# Power_Supply_Currentsensors.net
KiCad netlist of a schematic drawn in Altium Designer
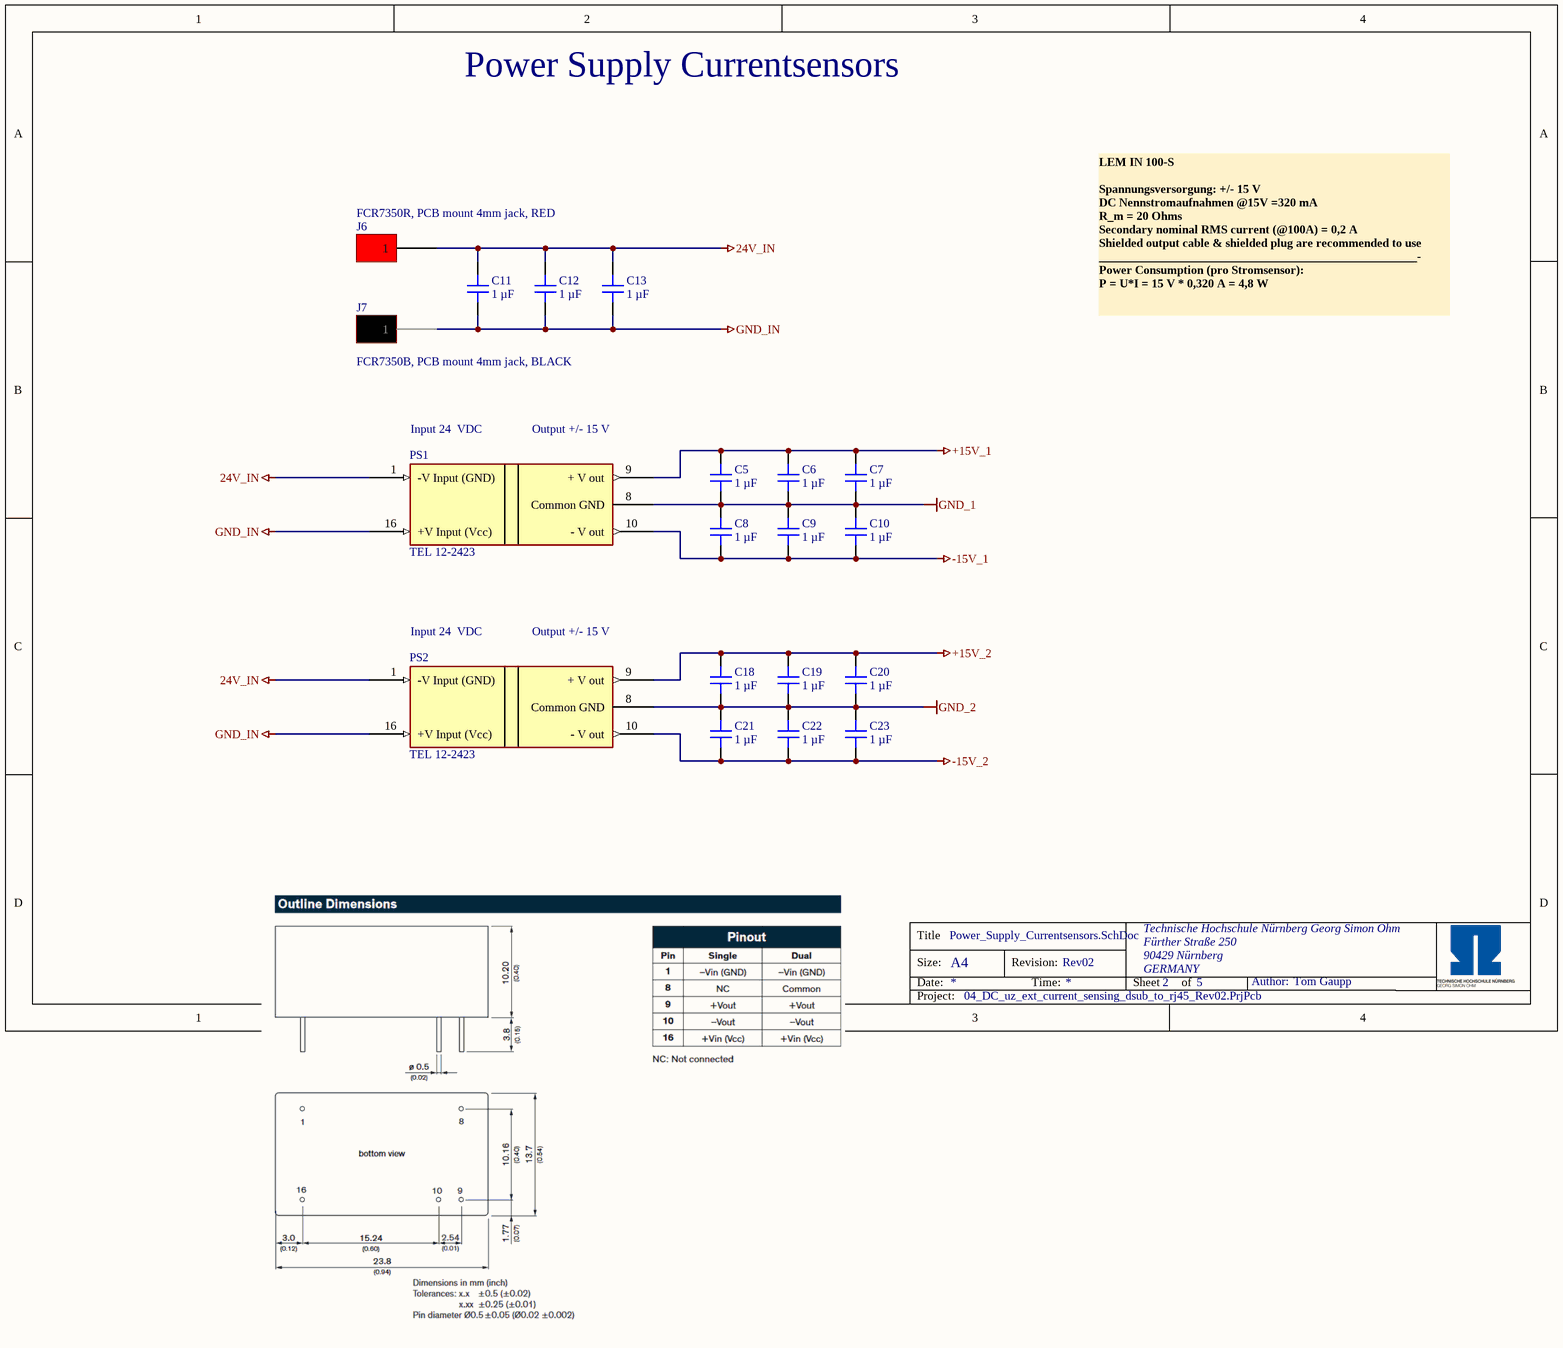
[diagram p0: Power_Supply_Currentsensors.SchDoc]

(export (version "E")
  (design (tool "Eeschema 10.0.6"))
  (components
    (comp (ref "C5")
      (value "1 µF")
      (footprint "C_0603")
      (description "50V 1uF X5R ±10% 0603  Multilayer Ceramic Capacitors MLCC - SMD/SMT ROHS")
      (fields
        (field (name "MANUFACTURER") "Samsung Electro-Mechanics")
        (field (name "MANUFACTURER PART NUMBER") "CL10A105KB8NNNC")
        (field (name "CREATED FROM") "MGremer")
      )
      (libsource (lib "user") (part "Capacitor"))
    )
    (comp (ref "C6")
      (value "1 µF")
      (footprint "C_0603")
      (description "50V 1uF X5R ±10% 0603  Multilayer Ceramic Capacitors MLCC - SMD/SMT ROHS")
      (fields
        (field (name "MANUFACTURER") "Samsung Electro-Mechanics")
        (field (name "MANUFACTURER PART NUMBER") "CL10A105KB8NNNC")
        (field (name "CREATED FROM") "MGremer")
      )
      (libsource (lib "user") (part "Capacitor"))
    )
    (comp (ref "C7")
      (value "1 µF")
      (footprint "C_0603")
      (description "50V 1uF X5R ±10% 0603  Multilayer Ceramic Capacitors MLCC - SMD/SMT ROHS")
      (fields
        (field (name "MANUFACTURER") "Samsung Electro-Mechanics")
        (field (name "MANUFACTURER PART NUMBER") "CL10A105KB8NNNC")
        (field (name "CREATED FROM") "MGremer")
      )
      (libsource (lib "user") (part "Capacitor"))
    )
    (comp (ref "C8")
      (value "1 µF")
      (footprint "C_0603")
      (description "50V 1uF X5R ±10% 0603  Multilayer Ceramic Capacitors MLCC - SMD/SMT ROHS")
      (fields
        (field (name "MANUFACTURER") "Samsung Electro-Mechanics")
        (field (name "MANUFACTURER PART NUMBER") "CL10A105KB8NNNC")
        (field (name "CREATED FROM") "MGremer")
      )
      (libsource (lib "user") (part "Capacitor"))
    )
    (comp (ref "C9")
      (value "1 µF")
      (footprint "C_0603")
      (description "50V 1uF X5R ±10% 0603  Multilayer Ceramic Capacitors MLCC - SMD/SMT ROHS")
      (fields
        (field (name "MANUFACTURER") "Samsung Electro-Mechanics")
        (field (name "MANUFACTURER PART NUMBER") "CL10A105KB8NNNC")
        (field (name "CREATED FROM") "MGremer")
      )
      (libsource (lib "user") (part "Capacitor"))
    )
    (comp (ref "C10")
      (value "1 µF")
      (footprint "C_0603")
      (description "50V 1uF X5R ±10% 0603  Multilayer Ceramic Capacitors MLCC - SMD/SMT ROHS")
      (fields
        (field (name "MANUFACTURER") "Samsung Electro-Mechanics")
        (field (name "MANUFACTURER PART NUMBER") "CL10A105KB8NNNC")
        (field (name "CREATED FROM") "MGremer")
      )
      (libsource (lib "user") (part "Capacitor"))
    )
    (comp (ref "C11")
      (value "1 µF")
      (footprint "C_0603")
      (description "50V 1uF X5R ±10% 0603  Multilayer Ceramic Capacitors MLCC - SMD/SMT ROHS")
      (fields
        (field (name "MANUFACTURER") "Samsung Electro-Mechanics")
        (field (name "MANUFACTURER PART NUMBER") "CL10A105KB8NNNC")
        (field (name "CREATED FROM") "MGremer")
      )
      (libsource (lib "user") (part "Capacitor"))
    )
    (comp (ref "C12")
      (value "1 µF")
      (footprint "C_0603")
      (description "50V 1uF X5R ±10% 0603  Multilayer Ceramic Capacitors MLCC - SMD/SMT ROHS")
      (fields
        (field (name "MANUFACTURER") "Samsung Electro-Mechanics")
        (field (name "MANUFACTURER PART NUMBER") "CL10A105KB8NNNC")
        (field (name "CREATED FROM") "MGremer")
      )
      (libsource (lib "user") (part "Capacitor"))
    )
    (comp (ref "C13")
      (value "1 µF")
      (footprint "C_0603")
      (description "50V 1uF X5R ±10% 0603  Multilayer Ceramic Capacitors MLCC - SMD/SMT ROHS")
      (fields
        (field (name "MANUFACTURER") "Samsung Electro-Mechanics")
        (field (name "MANUFACTURER PART NUMBER") "CL10A105KB8NNNC")
        (field (name "CREATED FROM") "MGremer")
      )
      (libsource (lib "user") (part "Capacitor"))
    )
    (comp (ref "C18")
      (value "1 µF")
      (footprint "C_0603")
      (description "50V 1uF X5R ±10% 0603  Multilayer Ceramic Capacitors MLCC - SMD/SMT ROHS")
      (fields
        (field (name "MANUFACTURER") "Samsung Electro-Mechanics")
        (field (name "MANUFACTURER PART NUMBER") "CL10A105KB8NNNC")
        (field (name "CREATED FROM") "MGremer")
      )
      (libsource (lib "user") (part "Capacitor"))
    )
    (comp (ref "C19")
      (value "1 µF")
      (footprint "C_0603")
      (description "50V 1uF X5R ±10% 0603  Multilayer Ceramic Capacitors MLCC - SMD/SMT ROHS")
      (fields
        (field (name "MANUFACTURER") "Samsung Electro-Mechanics")
        (field (name "MANUFACTURER PART NUMBER") "CL10A105KB8NNNC")
        (field (name "CREATED FROM") "MGremer")
      )
      (libsource (lib "user") (part "Capacitor"))
    )
    (comp (ref "C20")
      (value "1 µF")
      (footprint "C_0603")
      (description "50V 1uF X5R ±10% 0603  Multilayer Ceramic Capacitors MLCC - SMD/SMT ROHS")
      (fields
        (field (name "MANUFACTURER") "Samsung Electro-Mechanics")
        (field (name "MANUFACTURER PART NUMBER") "CL10A105KB8NNNC")
        (field (name "CREATED FROM") "MGremer")
      )
      (libsource (lib "user") (part "Capacitor"))
    )
    (comp (ref "C21")
      (value "1 µF")
      (footprint "C_0603")
      (description "50V 1uF X5R ±10% 0603  Multilayer Ceramic Capacitors MLCC - SMD/SMT ROHS")
      (fields
        (field (name "MANUFACTURER") "Samsung Electro-Mechanics")
        (field (name "MANUFACTURER PART NUMBER") "CL10A105KB8NNNC")
        (field (name "CREATED FROM") "MGremer")
      )
      (libsource (lib "user") (part "Capacitor"))
    )
    (comp (ref "C22")
      (value "1 µF")
      (footprint "C_0603")
      (description "50V 1uF X5R ±10% 0603  Multilayer Ceramic Capacitors MLCC - SMD/SMT ROHS")
      (fields
        (field (name "MANUFACTURER") "Samsung Electro-Mechanics")
        (field (name "MANUFACTURER PART NUMBER") "CL10A105KB8NNNC")
        (field (name "CREATED FROM") "MGremer")
      )
      (libsource (lib "user") (part "Capacitor"))
    )
    (comp (ref "C23")
      (value "1 µF")
      (footprint "C_0603")
      (description "50V 1uF X5R ±10% 0603  Multilayer Ceramic Capacitors MLCC - SMD/SMT ROHS")
      (fields
        (field (name "MANUFACTURER") "Samsung Electro-Mechanics")
        (field (name "MANUFACTURER PART NUMBER") "CL10A105KB8NNNC")
        (field (name "CREATED FROM") "MGremer")
      )
      (libsource (lib "user") (part "Capacitor"))
    )
    (comp (ref "J6")
      (value "FCR7350R, PCB mount 4mm jack, RED")
      (footprint "FCR7350")
      (description "FCR7350B, 1000V, 24A, RED")
      (fields
        (field (name "MANUFACTURER PART NUMBER") "FCR7350R")
        (field (name "MANUFACTURER") "Cliff")
        (field (name "CREATED FROM") "DHufnagel")
      )
      (libsource (lib "user") (part "FCR7350R"))
    )
    (comp (ref "J7")
      (value "FCR7350B, PCB mount 4mm jack, BLACK")
      (footprint "FCR7350")
      (description "FCR7350B, 1000V, 24A, BLACK")
      (fields
        (field (name "MANUFACTURER PART NUMBER") "FCR7350B")
        (field (name "MANUFACTURER") "Cliff")
        (field (name "CREATED FROM") "DHufnagel")
      )
      (libsource (lib "user") (part "FCR7350B"))
    )
    (comp (ref "PS1")
      (value "TEL 12-2423")
      (footprint "eigene_lib_alt:TEL 12-2423")
      (description "Isolierte DC/DC-Wandler – Durchsteckmontage 18-36Vin+/-15V 400mA 12W DIP Iso")
      (libsource (lib "eigene_lib_alt") (part "TEL 12-2423"))
    )
    (comp (ref "PS2")
      (value "TEL 12-2423")
      (footprint "eigene_lib_alt:TEL 12-2423")
      (description "Isolierte DC/DC-Wandler – Durchsteckmontage 18-36Vin+/-15V 400mA 12W DIP Iso")
      (libsource (lib "eigene_lib_alt") (part "TEL 12-2423"))
    )
  )
  (nets
    (net (code "1") (name "+15V_1") (class "Default")
      (node (ref "C5") (pin "2") (pinfunction "2_2") (pintype "passive"))
      (node (ref "C6") (pin "2") (pinfunction "2_2") (pintype "passive"))
      (node (ref "C7") (pin "2") (pinfunction "2_2") (pintype "passive"))
      (node (ref "PS1") (pin "9") (pinfunction "+_V_out_9") (pintype "output"))
    )
    (net (code "2") (name "+15V_2") (class "Default")
      (node (ref "C18") (pin "2") (pinfunction "2_2") (pintype "passive"))
      (node (ref "C19") (pin "2") (pinfunction "2_2") (pintype "passive"))
      (node (ref "C20") (pin "2") (pinfunction "2_2") (pintype "passive"))
      (node (ref "PS2") (pin "9") (pinfunction "+_V_out_9") (pintype "output"))
    )
    (net (code "3") (name "-15V_1") (class "Default")
      (node (ref "C10") (pin "1") (pinfunction "1_1") (pintype "passive"))
      (node (ref "C8") (pin "1") (pinfunction "1_1") (pintype "passive"))
      (node (ref "C9") (pin "1") (pinfunction "1_1") (pintype "passive"))
      (node (ref "PS1") (pin "10") (pinfunction "-_V_out_10") (pintype "output"))
    )
    (net (code "4") (name "-15V_2") (class "Default")
      (node (ref "C21") (pin "1") (pinfunction "1_1") (pintype "passive"))
      (node (ref "C22") (pin "1") (pinfunction "1_1") (pintype "passive"))
      (node (ref "C23") (pin "1") (pinfunction "1_1") (pintype "passive"))
      (node (ref "PS2") (pin "10") (pinfunction "-_V_out_10") (pintype "output"))
    )
    (net (code "5") (name "24V_IN") (class "Default")
      (node (ref "C11") (pin "1") (pinfunction "1_1") (pintype "passive"))
      (node (ref "C12") (pin "1") (pinfunction "1_1") (pintype "passive"))
      (node (ref "C13") (pin "1") (pinfunction "1_1") (pintype "passive"))
      (node (ref "J6") (pin "1") (pinfunction "1_1") (pintype "passive"))
      (node (ref "PS1") (pin "1") (pinfunction "-V_Input_(GND)_1") (pintype "input"))
      (node (ref "PS2") (pin "1") (pinfunction "-V_Input_(GND)_1") (pintype "input"))
    )
    (net (code "6") (name "GND_1") (class "Default")
      (node (ref "C10") (pin "2") (pinfunction "2_2") (pintype "passive"))
      (node (ref "C5") (pin "1") (pinfunction "1_1") (pintype "passive"))
      (node (ref "C6") (pin "1") (pinfunction "1_1") (pintype "passive"))
      (node (ref "C7") (pin "1") (pinfunction "1_1") (pintype "passive"))
      (node (ref "C8") (pin "2") (pinfunction "2_2") (pintype "passive"))
      (node (ref "C9") (pin "2") (pinfunction "2_2") (pintype "passive"))
      (node (ref "PS1") (pin "8") (pinfunction "Common_GND_8") (pintype "passive"))
    )
    (net (code "7") (name "GND_2") (class "Default")
      (node (ref "C18") (pin "1") (pinfunction "1_1") (pintype "passive"))
      (node (ref "C19") (pin "1") (pinfunction "1_1") (pintype "passive"))
      (node (ref "C20") (pin "1") (pinfunction "1_1") (pintype "passive"))
      (node (ref "C21") (pin "2") (pinfunction "2_2") (pintype "passive"))
      (node (ref "C22") (pin "2") (pinfunction "2_2") (pintype "passive"))
      (node (ref "C23") (pin "2") (pinfunction "2_2") (pintype "passive"))
      (node (ref "PS2") (pin "8") (pinfunction "Common_GND_8") (pintype "passive"))
    )
    (net (code "8") (name "GND_IN") (class "Default")
      (node (ref "C11") (pin "2") (pinfunction "2_2") (pintype "passive"))
      (node (ref "C12") (pin "2") (pinfunction "2_2") (pintype "passive"))
      (node (ref "C13") (pin "2") (pinfunction "2_2") (pintype "passive"))
      (node (ref "J7") (pin "1") (pinfunction "1_1") (pintype "passive"))
      (node (ref "PS1") (pin "16") (pinfunction "+V_Input_(Vcc)_16") (pintype "input"))
      (node (ref "PS2") (pin "16") (pinfunction "+V_Input_(Vcc)_16") (pintype "input"))
    )
  )
)
